# RLCD_SCH_28LED_v1p13p2.net
KiCad netlist of a schematic drawn in Altium Designer
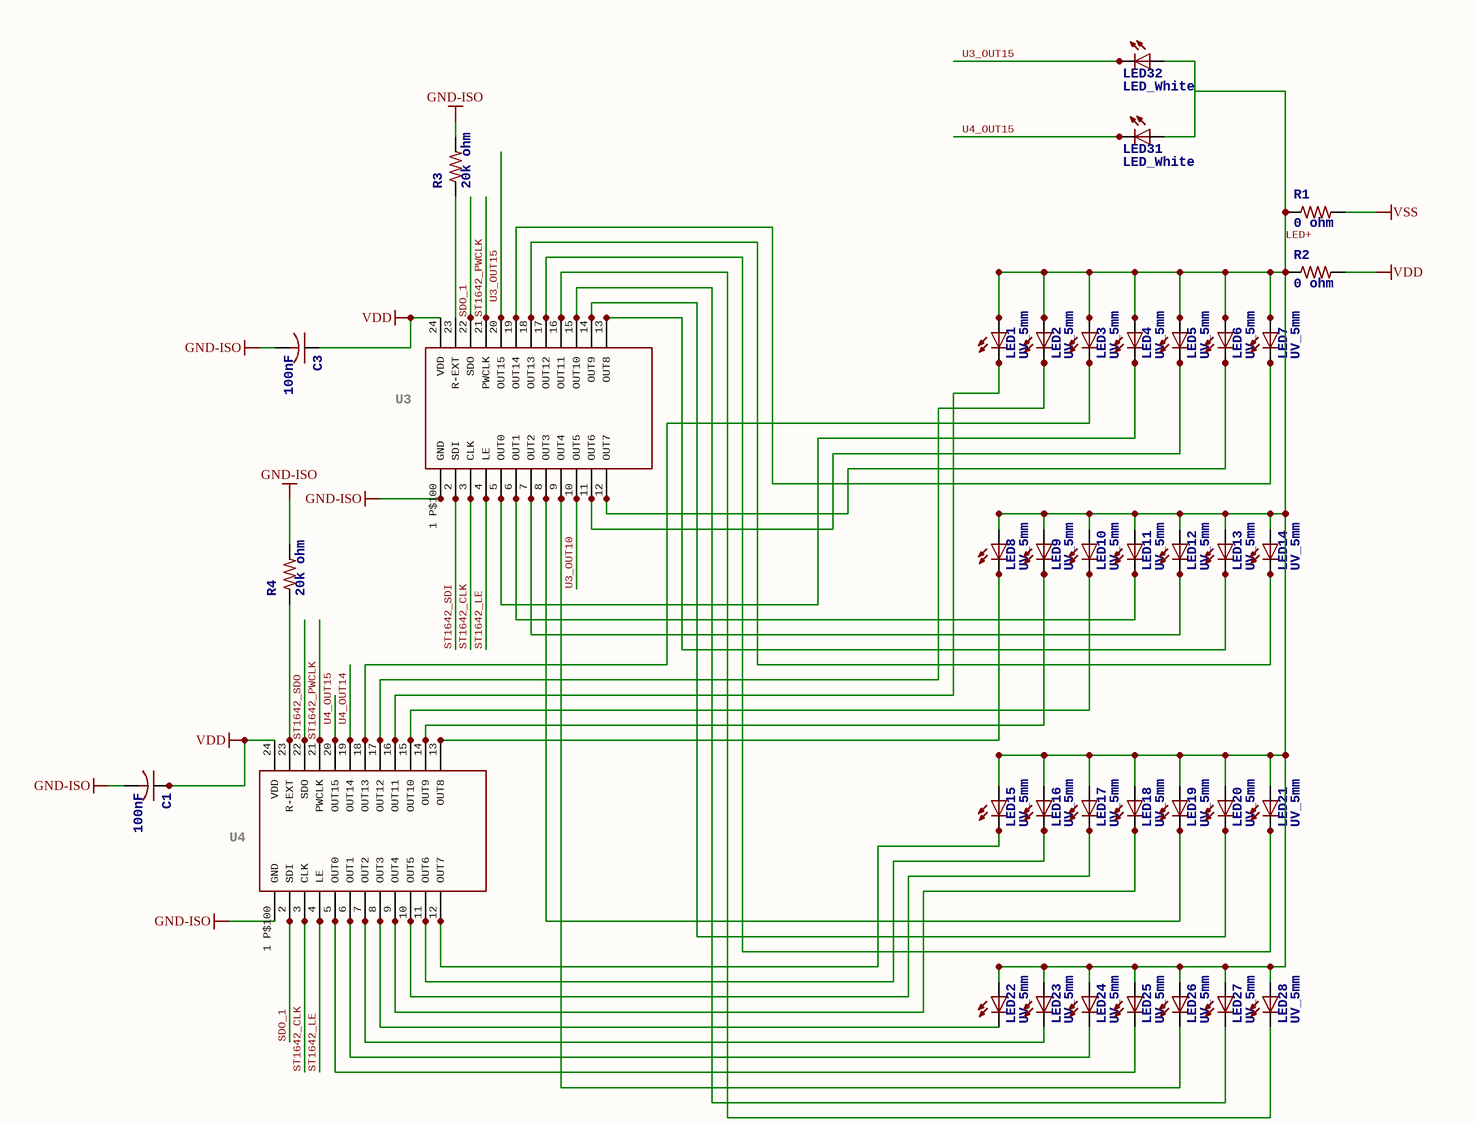
[diagram p0: RLCD_SCH_28LED_v1p13p2.SchDoc, top left]
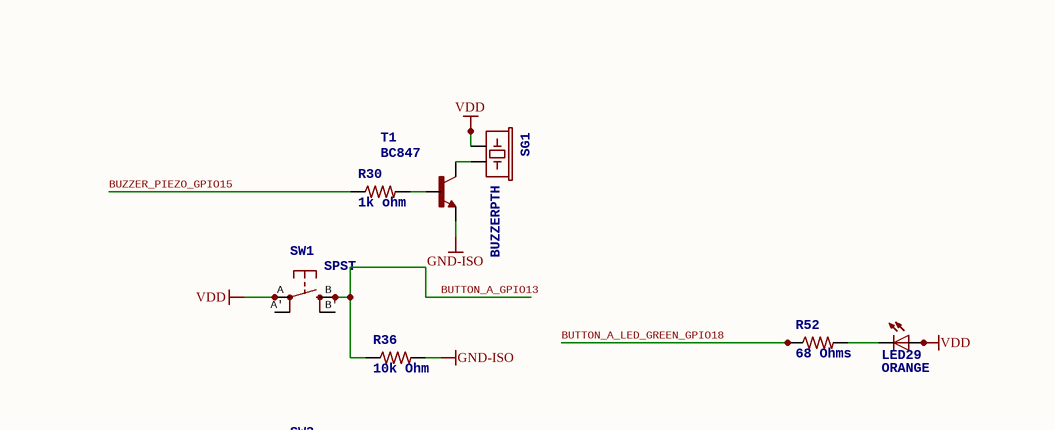
[diagram p1: RLCD_SCH_28LED_v1p13p2.SchDoc, top right]
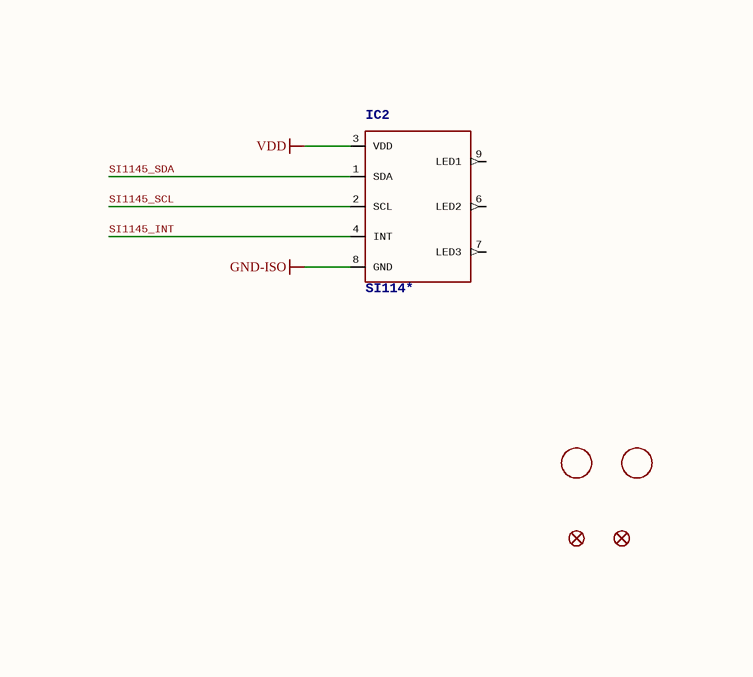
[diagram p2: RLCD_SCH_28LED_v1p13p2.SchDoc, bottom left]
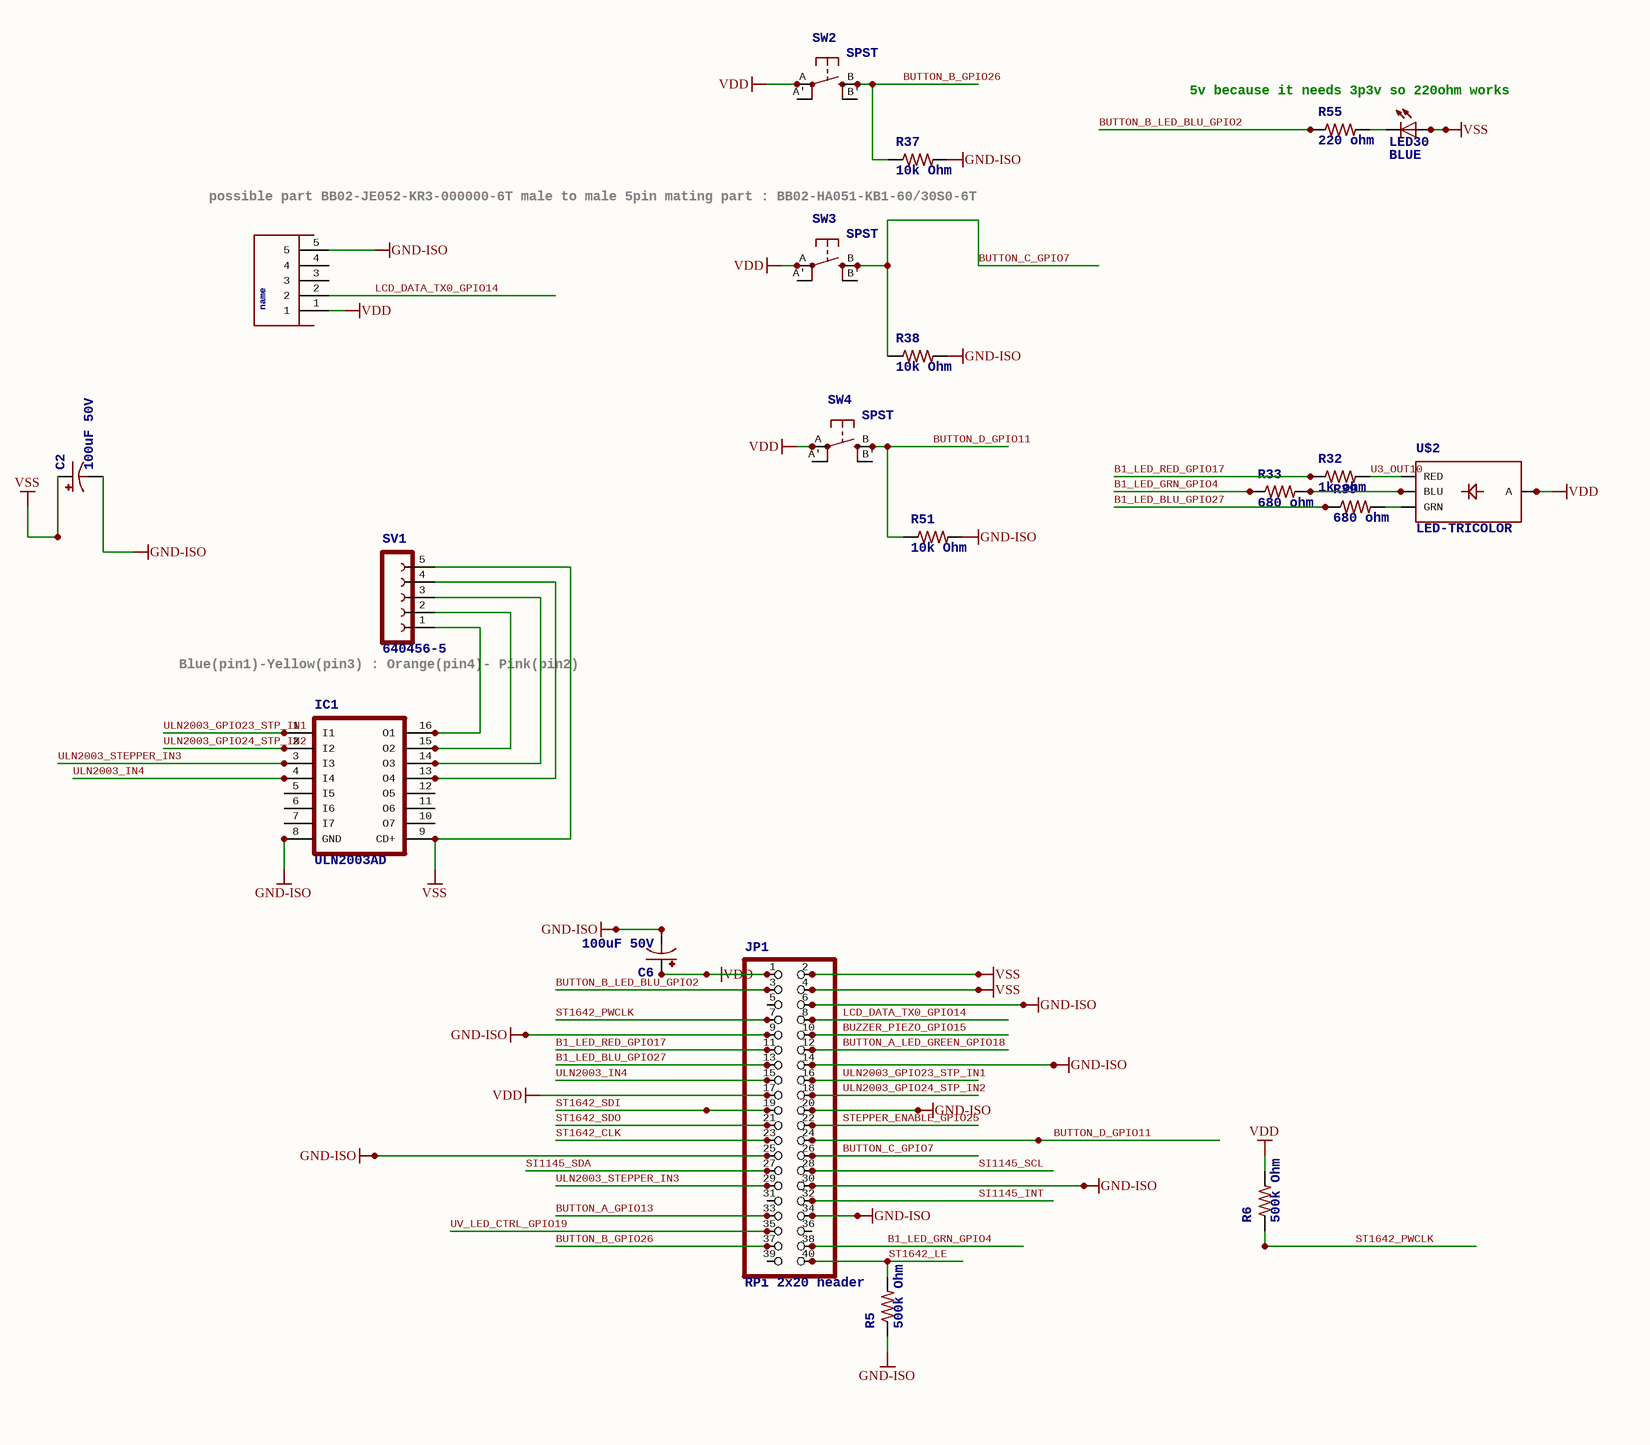
[diagram p3: RLCD_SCH_28LED_v1p13p2.SchDoc, bottom right]

(export (version "E")
  (design (tool "Eeschema 10.0.6"))
  (components
    (comp (ref "C1")
      (value "100nF")
      (footprint "C0805")
      (description "<B>CAPACITOR</B>, American symbol")
      (fields (field (name ">NAME") "C1") (field (name ">VALUE") "100nF"))
      (libsource (lib "resistor") (part "C-USC0805"))
    )
    (comp (ref "C2")
      (value "100uF 50V")
      (footprint "E3,5-8")
      (description "<B>POLARIZED CAPACITOR</B>, American symbol")
      (fields
        (field (name "PARTNO") "REA101M1HBK-0811P")
        (field (name ">NAME") "C2")
        (field (name ">VALUE") "100uF 50V")
      )
      (libsource (lib "") (part "CPOL-USE3.5-8_1"))
    )
    (comp (ref "C3")
      (value "100nF")
      (footprint "C0805")
      (description "<B>CAPACITOR</B>, American symbol")
      (fields (field (name ">NAME") "C3") (field (name ">VALUE") "100nF"))
      (libsource (lib "resistor") (part "C-USC0805"))
    )
    (comp (ref "C6")
      (value "100uF 50V")
      (footprint "E3,5-8")
      (description "<B>POLARIZED CAPACITOR</B>, American symbol")
      (fields
        (field (name "PARTNO") "REA101M1HBK-0811P")
        (field (name ">NAME") "C6")
        (field (name ">VALUE") "100uF 50V")
      )
      (libsource (lib "adafruit") (part "CPOL-USE3.5-8"))
    )
    (comp (ref "FID1")
      (value "FIDUCIAL1X2")
      (footprint "FIDUCIAL-1X2")
      (description "<b>Fiducial Alignment Points</b>\nVarious fiducial points for machine vision alignment.")
      (libsource (lib "SparkFun-Aesthetics") (part "FIDUCIAL1X2"))
    )
    (comp (ref "FID2")
      (value "FIDUCIAL1X2")
      (footprint "FIDUCIAL-1X2")
      (description "<b>Fiducial Alignment Points</b>\nVarious fiducial points for machine vision alignment.")
      (libsource (lib "SparkFun-Aesthetics") (part "FIDUCIAL1X2"))
    )
    (comp (ref "IC1")
      (value "ULN2003AD")
      (footprint "SO16")
      (description "<b>DRIVER ARRAY</b>")
      (fields (field (name ">NAME") "IC1") (field (name ">VALUE") "ULN2003AD"))
      (libsource (lib "uln-udn") (part "ULN2003AD"))
    )
    (comp (ref "IC2")
      (value "SI114*")
      (footprint "QFN-10")
      (fields (field (name ">NAME") "IC2") (field (name ">VALUE") "SI114*"))
      (libsource (lib "silabs") (part "SI114*"))
    )
    (comp (ref "JP1")
      (value "RPi 2x20 header")
      (footprint "2X20")
      (description "<b>PIN HEADER</b>")
      (fields
        (field (name "PARTNO") "929975-01-13-RK")
        (field (name ">NAME") "JP1")
        (field (name ">VALUE") "RPi 2x20 header")
      )
      (libsource (lib "adafruit") (part "PINHD-2X20"))
    )
    (comp (ref "LED1")
      (value "UV_5mm")
      (footprint "LED5MM")
      (fields (field (name ">NAME") "LED1") (field (name ">VALUE") "UV_5mm"))
      (libsource (lib "led") (part "LED5MM"))
    )
    (comp (ref "LED2")
      (value "UV_5mm")
      (footprint "LED5MM")
      (fields (field (name ">NAME") "LED2") (field (name ">VALUE") "UV_5mm"))
      (libsource (lib "led") (part "LED5MM"))
    )
    (comp (ref "LED3")
      (value "UV_5mm")
      (footprint "LED5MM")
      (fields (field (name ">NAME") "LED3") (field (name ">VALUE") "UV_5mm"))
      (libsource (lib "led") (part "LED5MM"))
    )
    (comp (ref "LED4")
      (value "UV_5mm")
      (footprint "LED5MM")
      (fields (field (name ">NAME") "LED4") (field (name ">VALUE") "UV_5mm"))
      (libsource (lib "led") (part "LED5MM"))
    )
    (comp (ref "LED5")
      (value "UV_5mm")
      (footprint "LED5MM")
      (fields (field (name ">NAME") "LED5") (field (name ">VALUE") "UV_5mm"))
      (libsource (lib "led") (part "LED5MM"))
    )
    (comp (ref "LED6")
      (value "UV_5mm")
      (footprint "LED5MM")
      (fields (field (name ">NAME") "LED6") (field (name ">VALUE") "UV_5mm"))
      (libsource (lib "led") (part "LED5MM"))
    )
    (comp (ref "LED7")
      (value "UV_5mm")
      (footprint "LED5MM")
      (fields (field (name ">NAME") "LED7") (field (name ">VALUE") "UV_5mm"))
      (libsource (lib "led") (part "LED5MM"))
    )
    (comp (ref "LED8")
      (value "UV_5mm")
      (footprint "LED5MM")
      (fields (field (name ">NAME") "LED8") (field (name ">VALUE") "UV_5mm"))
      (libsource (lib "led") (part "LED5MM"))
    )
    (comp (ref "LED9")
      (value "UV_5mm")
      (footprint "LED5MM")
      (fields (field (name ">NAME") "LED9") (field (name ">VALUE") "UV_5mm"))
      (libsource (lib "led") (part "LED5MM"))
    )
    (comp (ref "LED10")
      (value "UV_5mm")
      (footprint "LED5MM")
      (fields (field (name ">NAME") "LED10") (field (name ">VALUE") "UV_5mm"))
      (libsource (lib "led") (part "LED5MM"))
    )
    (comp (ref "LED11")
      (value "UV_5mm")
      (footprint "LED5MM")
      (fields (field (name ">NAME") "LED11") (field (name ">VALUE") "UV_5mm"))
      (libsource (lib "led") (part "LED5MM"))
    )
    (comp (ref "LED12")
      (value "UV_5mm")
      (footprint "LED5MM")
      (fields (field (name ">NAME") "LED12") (field (name ">VALUE") "UV_5mm"))
      (libsource (lib "led") (part "LED5MM"))
    )
    (comp (ref "LED13")
      (value "UV_5mm")
      (footprint "LED5MM")
      (fields (field (name ">NAME") "LED13") (field (name ">VALUE") "UV_5mm"))
      (libsource (lib "led") (part "LED5MM"))
    )
    (comp (ref "LED14")
      (value "UV_5mm")
      (footprint "LED5MM")
      (fields (field (name ">NAME") "LED14") (field (name ">VALUE") "UV_5mm"))
      (libsource (lib "led") (part "LED5MM"))
    )
    (comp (ref "LED15")
      (value "UV_5mm")
      (footprint "LED5MM")
      (fields (field (name ">NAME") "LED15") (field (name ">VALUE") "UV_5mm"))
      (libsource (lib "led") (part "LED5MM"))
    )
    (comp (ref "LED16")
      (value "UV_5mm")
      (footprint "LED5MM")
      (fields (field (name ">NAME") "LED16") (field (name ">VALUE") "UV_5mm"))
      (libsource (lib "led") (part "LED5MM"))
    )
    (comp (ref "LED17")
      (value "UV_5mm")
      (footprint "LED5MM")
      (fields (field (name ">NAME") "LED17") (field (name ">VALUE") "UV_5mm"))
      (libsource (lib "led") (part "LED5MM"))
    )
    (comp (ref "LED18")
      (value "UV_5mm")
      (footprint "LED5MM")
      (fields (field (name ">NAME") "LED18") (field (name ">VALUE") "UV_5mm"))
      (libsource (lib "led") (part "LED5MM"))
    )
    (comp (ref "LED19")
      (value "UV_5mm")
      (footprint "LED5MM")
      (fields (field (name ">NAME") "LED19") (field (name ">VALUE") "UV_5mm"))
      (libsource (lib "led") (part "LED5MM"))
    )
    (comp (ref "LED20")
      (value "UV_5mm")
      (footprint "LED5MM")
      (fields (field (name ">NAME") "LED20") (field (name ">VALUE") "UV_5mm"))
      (libsource (lib "led") (part "LED5MM"))
    )
    (comp (ref "LED21")
      (value "UV_5mm")
      (footprint "LED5MM")
      (fields (field (name ">NAME") "LED21") (field (name ">VALUE") "UV_5mm"))
      (libsource (lib "led") (part "LED5MM"))
    )
    (comp (ref "LED22")
      (value "UV_5mm")
      (footprint "LED5MM")
      (fields (field (name ">NAME") "LED22") (field (name ">VALUE") "UV_5mm"))
      (libsource (lib "led") (part "LED5MM"))
    )
    (comp (ref "LED23")
      (value "UV_5mm")
      (footprint "LED5MM")
      (fields (field (name ">NAME") "LED23") (field (name ">VALUE") "UV_5mm"))
      (libsource (lib "led") (part "LED5MM"))
    )
    (comp (ref "LED24")
      (value "UV_5mm")
      (footprint "LED5MM")
      (fields (field (name ">NAME") "LED24") (field (name ">VALUE") "UV_5mm"))
      (libsource (lib "led") (part "LED5MM"))
    )
    (comp (ref "LED25")
      (value "UV_5mm")
      (footprint "LED5MM")
      (fields (field (name ">NAME") "LED25") (field (name ">VALUE") "UV_5mm"))
      (libsource (lib "led") (part "LED5MM"))
    )
    (comp (ref "LED26")
      (value "UV_5mm")
      (footprint "LED5MM")
      (fields (field (name ">NAME") "LED26") (field (name ">VALUE") "UV_5mm"))
      (libsource (lib "led") (part "LED5MM"))
    )
    (comp (ref "LED27")
      (value "UV_5mm")
      (footprint "LED5MM")
      (fields (field (name ">NAME") "LED27") (field (name ">VALUE") "UV_5mm"))
      (libsource (lib "led") (part "LED5MM"))
    )
    (comp (ref "LED28")
      (value "UV_5mm")
      (footprint "LED5MM")
      (fields (field (name ">NAME") "LED28") (field (name ">VALUE") "UV_5mm"))
      (libsource (lib "led") (part "LED5MM"))
    )
    (comp (ref "LED29")
      (value "ORANGE")
      (footprint "CHIPLED_1206")
      (fields
        (field (name "PARTNO") "LG N971-KN-1")
        (field (name ">NAME") "LED29")
        (field (name ">VALUE") "ORANGE")
      )
      (libsource (lib "adafruit") (part "LEDCHIPLED_1206"))
    )
    (comp (ref "LED30")
      (value "BLUE")
      (footprint "CHIPLED_1206")
      (fields
        (field (name "PARTNO") "LTST-C21TBKT")
        (field (name ">NAME") "LED30")
        (field (name ">VALUE") "BLUE")
      )
      (libsource (lib "adafruit") (part "LEDCHIPLED_1206"))
    )
    (comp (ref "LED31")
      (value "LED_White")
      (footprint "CHIPLED_1206")
      (fields
        (field (name "PARTNO") "LG N971-KN-1")
        (field (name ">NAME") "LED31")
        (field (name ">VALUE") "LED_White")
      )
      (libsource (lib "adafruit") (part "LEDCHIPLED_1206"))
    )
    (comp (ref "LED32")
      (value "LED_White")
      (footprint "CHIPLED_1206")
      (fields
        (field (name "PARTNO") "LG N971-KN-1")
        (field (name ">NAME") "LED32")
        (field (name ">VALUE") "LED_White")
      )
      (libsource (lib "adafruit") (part "LEDCHIPLED_1206"))
    )
    (comp (ref "R1")
      (value "0 ohm")
      (footprint "0805")
      (description "<b>Resistor</b>\nBasic schematic elements and footprints for 0603, 1206, and PTH resistors.")
      (fields (field (name "PARTNO") "DNP") (field (name ">NAME") "R1") (field (name ">VALUE") "0 ohm"))
      (libsource (lib "SparkFun-Passives") (part "RESISTOR0805-RES"))
    )
    (comp (ref "R2")
      (value "0 ohm")
      (footprint "0805")
      (description "<b>Resistor</b>\nBasic schematic elements and footprints for 0603, 1206, and PTH resistors.")
      (fields (field (name "PARTNO") "DNP") (field (name ">NAME") "R2") (field (name ">VALUE") "0 ohm"))
      (libsource (lib "SparkFun-Passives") (part "RESISTOR0805-RES"))
    )
    (comp (ref "R3")
      (value "20k ohm")
      (footprint "0805")
      (description "<b>Resistor</b>\nBasic schematic elements and footprints for 0603, 1206, and PTH resistors.")
      (fields (field (name "PARTNO") "DNP") (field (name ">NAME") "R3") (field (name ">VALUE") "20k ohm"))
      (libsource (lib "SparkFun-Passives") (part "RESISTOR0805-RES"))
    )
    (comp (ref "R4")
      (value "20k ohm")
      (footprint "0805")
      (description "<b>Resistor</b>\nBasic schematic elements and footprints for 0603, 1206, and PTH resistors.")
      (fields (field (name "PARTNO") "DNP") (field (name ">NAME") "R4") (field (name ">VALUE") "20k ohm"))
      (libsource (lib "SparkFun-Passives") (part "RESISTOR0805-RES"))
    )
    (comp (ref "R5")
      (value "500k Ohm")
      (footprint "0805")
      (description "<b>Resistor</b>\nBasic schematic elements and footprints for 0603, 1206, and PTH resistors.")
      (fields
        (field (name "PARTNO") "RK73B2ATTD103J")
        (field (name ">NAME") "R5")
        (field (name ">VALUE") "500k Ohm")
      )
      (libsource (lib "SparkFun-Passives") (part "RESISTOR0805-RES"))
    )
    (comp (ref "R6")
      (value "500k Ohm")
      (footprint "0805")
      (description "<b>Resistor</b>\nBasic schematic elements and footprints for 0603, 1206, and PTH resistors.")
      (fields
        (field (name "PARTNO") "RK73B2ATTD103J")
        (field (name ">NAME") "R6")
        (field (name ">VALUE") "500k Ohm")
      )
      (libsource (lib "SparkFun-Passives") (part "RESISTOR0805-RES"))
    )
    (comp (ref "R30")
      (value "1k ohm")
      (footprint "0805")
      (description "<b>Resistor</b>\nBasic schematic elements and footprints for 0603, 1206, and PTH resistors.")
      (fields
        (field (name "PARTNO") "RK73H2ATTD1001F")
        (field (name ">NAME") "R30")
        (field (name ">VALUE") "1k ohm")
      )
      (libsource (lib "SparkFun-Passives") (part "RESISTOR0805-RES"))
    )
    (comp (ref "R32")
      (value "1k ohm")
      (footprint "0805")
      (description "<b>Resistor</b>\nBasic schematic elements and footprints for 0603, 1206, and PTH resistors.")
      (fields
        (field (name "PARTNO") "RK73H2ATTD1001F")
        (field (name ">NAME") "R32")
        (field (name ">VALUE") "1k ohm")
      )
      (libsource (lib "SparkFun-Passives") (part "RESISTOR0805-RES"))
    )
    (comp (ref "R33")
      (value "680 ohm")
      (footprint "0805")
      (description "<b>Resistor</b>\nBasic schematic elements and footprints for 0603, 1206, and PTH resistors.")
      (fields
        (field (name "PARTNO") "RK73B2ATTD681J")
        (field (name ">NAME") "R33")
        (field (name ">VALUE") "680 ohm")
      )
      (libsource (lib "SparkFun-Passives") (part "RESISTOR0805-RES"))
    )
    (comp (ref "R36")
      (value "10k Ohm")
      (footprint "0805")
      (description "<b>Resistor</b>\nBasic schematic elements and footprints for 0603, 1206, and PTH resistors.")
      (fields
        (field (name "PARTNO") "RK73B2ATTD103J")
        (field (name ">NAME") "R36")
        (field (name ">VALUE") "10k Ohm")
      )
      (libsource (lib "SparkFun-Passives") (part "RESISTOR0805-RES"))
    )
    (comp (ref "R37")
      (value "10k Ohm")
      (footprint "0805")
      (description "<b>Resistor</b>\nBasic schematic elements and footprints for 0603, 1206, and PTH resistors.")
      (fields
        (field (name "PARTNO") "RK73B2ATTD103J")
        (field (name ">NAME") "R37")
        (field (name ">VALUE") "10k Ohm")
      )
      (libsource (lib "SparkFun-Passives") (part "RESISTOR0805-RES"))
    )
    (comp (ref "R38")
      (value "10k Ohm")
      (footprint "0805")
      (description "<b>Resistor</b>\nBasic schematic elements and footprints for 0603, 1206, and PTH resistors.")
      (fields
        (field (name "PARTNO") "RK73B2ATTD103J")
        (field (name ">NAME") "R38")
        (field (name ">VALUE") "10k Ohm")
      )
      (libsource (lib "SparkFun-Passives") (part "RESISTOR0805-RES"))
    )
    (comp (ref "R39")
      (value "680 ohm")
      (footprint "0805")
      (description "<b>Resistor</b>\nBasic schematic elements and footprints for 0603, 1206, and PTH resistors.")
      (fields
        (field (name "PARTNO") "RK73B2ATTD681J")
        (field (name ">NAME") "R39")
        (field (name ">VALUE") "680 ohm")
      )
      (libsource (lib "SparkFun-Passives") (part "RESISTOR0805-RES"))
    )
    (comp (ref "R51")
      (value "10k Ohm")
      (footprint "0805")
      (description "<b>Resistor</b>\nBasic schematic elements and footprints for 0603, 1206, and PTH resistors.")
      (fields
        (field (name "PARTNO") "RK73B2ATTD103J")
        (field (name ">NAME") "R51")
        (field (name ">VALUE") "10k Ohm")
      )
      (libsource (lib "SparkFun-Passives") (part "RESISTOR0805-RES"))
    )
    (comp (ref "R52")
      (value "68 Ohms")
      (footprint "0805")
      (description "<b>Resistor</b>\nBasic schematic elements and footprints for 0603, 1206, and PTH resistors.")
      (fields
        (field (name "PARTNO") "RK73B2ATTDD121J")
        (field (name ">NAME") "R52")
        (field (name ">VALUE") "68 Ohms")
      )
      (libsource (lib "SparkFun-Passives") (part "RESISTOR0805-RES"))
    )
    (comp (ref "R55")
      (value "220 ohm")
      (footprint "0805")
      (description "<b>Resistor</b>\nBasic schematic elements and footprints for 0603, 1206, and PTH resistors.")
      (fields
        (field (name "PARTNO") "RK73B2ATTD221J")
        (field (name ">NAME") "R55")
        (field (name ">VALUE") "220 ohm")
      )
      (libsource (lib "SparkFun-Passives") (part "RESISTOR0805-RES"))
    )
    (comp (ref "SG1")
      (value "BUZZERPTH")
      (footprint "BUZZER-12MM")
      (description "<b>Buzzer 12mm</b>\nSpark Fun Electronics SKU : Comp-Buzzer")
      (fields
        (field (name "PARTNO") "AT-1220-TT-R")
        (field (name ">NAME") "SG1")
        (field (name ">VALUE") "BUZZERPTH")
      )
      (libsource (lib "SparkFun-Electromechanical") (part "BUZZERPTH"))
    )
    (comp (ref "SV1")
      (value "640456-5")
      (footprint "FE05-1")
      (description "<b>FEMALE HEADER</b>")
      (fields (field (name ">VALUE") "640456-5") (field (name ">NAME") "SV1"))
      (libsource (lib "con-lsta") (part "FE05-1"))
    )
    (comp (ref "SV3_LCD_HEADER")
      (value "22-05-2051")
      (footprint "MDF7-5S-2.54DSA")
      (fields (field (name "PARTNO") "MDF7-5S-2.54DSA(55)") (field (name "NAME") "name"))
      (libsource (lib "Trents_Hirose_5pin_2.54mm_Connector") (part "MDF7-5S-2.54DSA"))
    )
    (comp (ref "SW1")
      (value "SPST")
      (footprint "EVQ-Q2")
      (description "SMT 6mm switch, EVQQ2 series\n<p>http://www.ladyada.net/library/eagle</p>")
      (fields (field (name ">NAME") "SW1") (field (name ">VALUE") "SPST"))
      (libsource (lib "adafruit") (part "SPST_TACT-EVQQ2"))
    )
    (comp (ref "SW2")
      (value "SPST")
      (footprint "EVQ-Q2")
      (description "SMT 6mm switch, EVQQ2 series\n<p>http://www.ladyada.net/library/eagle</p>")
      (fields (field (name ">NAME") "SW2") (field (name ">VALUE") "SPST"))
      (libsource (lib "adafruit") (part "SPST_TACT-EVQQ2"))
    )
    (comp (ref "SW3")
      (value "SPST")
      (footprint "EVQ-Q2")
      (description "SMT 6mm switch, EVQQ2 series\n<p>http://www.ladyada.net/library/eagle</p>")
      (fields (field (name ">NAME") "SW3") (field (name ">VALUE") "SPST"))
      (libsource (lib "adafruit") (part "SPST_TACT-EVQQ2"))
    )
    (comp (ref "SW4")
      (value "SPST")
      (footprint "EVQ-Q2")
      (description "SMT 6mm switch, EVQQ2 series\n<p>http://www.ladyada.net/library/eagle</p>")
      (fields (field (name ">NAME") "SW4") (field (name ">VALUE") "SPST"))
      (libsource (lib "adafruit") (part "SPST_TACT-EVQQ2"))
    )
    (comp (ref "T1")
      (value "BC847")
      (footprint "SOT23")
      (description "<b>NPN TRANSISTOR</b>")
      (fields
        (field (name "PARTNO") "MMUN2214LT1G")
        (field (name ">NAME") "T1")
        (field (name ">VALUE") "BC847")
      )
      (libsource (lib "transistor") (part "BC847"))
    )
    (comp (ref "U$1")
      (value "FIDUCIAL")
      (footprint "FIDUCIAL_1MM")
      (description "For use by pick and place machines to calibrate the vision/machine, 1mm\n<p>By microbuilder.eu</p>")
      (libsource (lib "adafruit") (part "FIDUCIAL"))
    )
    (comp (ref "U$2")
      (value "LED-TRICOLOR")
      (footprint "LED-TRICOLOR-SMD")
      (fields
        (field (name "PARTNO") "CLV1A-FKB-CHMKPEHBB7A363")
        (field (name ">NAME") "U$2")
        (field (name ">VALUE") "LED-TRICOLOR")
      )
      (libsource (lib "SparkFun-LED") (part "LED-TRICOLOR"))
    )
    (comp (ref "U$3")
      (value "LED1642GWTTR")
      (footprint "TSSOP24")
      (libsource (lib "iBox_Nano_Custom_Components") (part "LED1642GWTTR"))
    )
    (comp (ref "U$4")
      (value "LED1642GWTTR")
      (footprint "TSSOP24")
      (libsource (lib "iBox_Nano_Custom_Components") (part "LED1642GWTTR"))
    )
    (comp (ref "U$5")
      (value "FIDUCIAL")
      (footprint "FIDUCIAL_1MM")
      (description "For use by pick and place machines to calibrate the vision/machine, 1mm\n<p>By microbuilder.eu</p>")
      (libsource (lib "adafruit") (part "FIDUCIAL"))
    )
  )
  (nets
    (net (code "1") (name "/B1_LED_BLU_GPIO27") (class "Default")
      (node (ref "JP1") (pin "13") (pinfunction "13_13") (pintype "passive"))
      (node (ref "R39") (pin "1") (pinfunction "1_1") (pintype "passive"))
    )
    (net (code "2") (name "/B1_LED_GRN_GPIO4") (class "Default")
      (node (ref "JP1") (pin "38") (pinfunction "38_38") (pintype "passive"))
      (node (ref "R33") (pin "1") (pinfunction "1_1") (pintype "passive"))
    )
    (net (code "3") (name "/B1_LED_RED_GPIO17") (class "Default")
      (node (ref "JP1") (pin "11") (pinfunction "11_11") (pintype "passive"))
      (node (ref "R32") (pin "1") (pinfunction "1_1") (pintype "passive"))
    )
    (net (code "4") (name "/BUTTON_A_GPIO13") (class "Default")
      (node (ref "JP1") (pin "33") (pinfunction "33_33") (pintype "passive"))
      (node (ref "R36") (pin "1") (pinfunction "1_1") (pintype "passive"))
      (node (ref "SW1") (pin "B") (pinfunction "S_B") (pintype "passive"))
    )
    (net (code "5") (name "/BUTTON_A_LED_GREEN_GPIO18") (class "Default")
      (node (ref "JP1") (pin "12") (pinfunction "12_12") (pintype "passive"))
      (node (ref "R52") (pin "1") (pinfunction "1_1") (pintype "passive"))
    )
    (net (code "6") (name "/BUTTON_B_GPIO26") (class "Default")
      (node (ref "JP1") (pin "37") (pinfunction "37_37") (pintype "passive"))
      (node (ref "R37") (pin "1") (pinfunction "1_1") (pintype "passive"))
      (node (ref "SW2") (pin "B") (pinfunction "S_B") (pintype "passive"))
    )
    (net (code "7") (name "/BUTTON_B_LED_BLU_GPIO2") (class "Default")
      (node (ref "JP1") (pin "3") (pinfunction "3_3") (pintype "passive"))
      (node (ref "R55") (pin "1") (pinfunction "1_1") (pintype "passive"))
    )
    (net (code "8") (name "/BUTTON_C_GPIO7") (class "Default")
      (node (ref "JP1") (pin "26") (pinfunction "26_26") (pintype "passive"))
      (node (ref "R38") (pin "1") (pinfunction "1_1") (pintype "passive"))
      (node (ref "SW3") (pin "B") (pinfunction "S_B") (pintype "passive"))
    )
    (net (code "9") (name "/BUTTON_D_GPIO11") (class "Default")
      (node (ref "JP1") (pin "24") (pinfunction "24_24") (pintype "passive"))
      (node (ref "R51") (pin "1") (pinfunction "1_1") (pintype "passive"))
      (node (ref "SW4") (pin "B") (pinfunction "S_B") (pintype "passive"))
    )
    (net (code "10") (name "/BUZZER_PIEZO_GPIO15") (class "Default")
      (node (ref "JP1") (pin "10") (pinfunction "10_10") (pintype "passive"))
      (node (ref "R30") (pin "1") (pinfunction "1_1") (pintype "passive"))
    )
    (net (code "11") (name "/LCD_DATA_TX0_GPIO14") (class "Default")
      (node (ref "JP1") (pin "8") (pinfunction "8_8") (pintype "passive"))
      (node (ref "SV3_LCD_HEADER") (pin "2") (pinfunction "2_2") (pintype "passive"))
    )
    (net (code "12") (name "/LED+") (class "Default")
      (node (ref "LED1") (pin "A") (pinfunction "A_A") (pintype "passive"))
      (node (ref "LED10") (pin "A") (pinfunction "A_A") (pintype "passive"))
      (node (ref "LED11") (pin "A") (pinfunction "A_A") (pintype "passive"))
      (node (ref "LED12") (pin "A") (pinfunction "A_A") (pintype "passive"))
      (node (ref "LED13") (pin "A") (pinfunction "A_A") (pintype "passive"))
      (node (ref "LED14") (pin "A") (pinfunction "A_A") (pintype "passive"))
      (node (ref "LED15") (pin "A") (pinfunction "A_A") (pintype "passive"))
      (node (ref "LED16") (pin "A") (pinfunction "A_A") (pintype "passive"))
      (node (ref "LED17") (pin "A") (pinfunction "A_A") (pintype "passive"))
      (node (ref "LED18") (pin "A") (pinfunction "A_A") (pintype "passive"))
      (node (ref "LED19") (pin "A") (pinfunction "A_A") (pintype "passive"))
      (node (ref "LED2") (pin "A") (pinfunction "A_A") (pintype "passive"))
      (node (ref "LED20") (pin "A") (pinfunction "A_A") (pintype "passive"))
      (node (ref "LED21") (pin "A") (pinfunction "A_A") (pintype "passive"))
      (node (ref "LED22") (pin "A") (pinfunction "A_A") (pintype "passive"))
      (node (ref "LED23") (pin "A") (pinfunction "A_A") (pintype "passive"))
      (node (ref "LED24") (pin "A") (pinfunction "A_A") (pintype "passive"))
      (node (ref "LED25") (pin "A") (pinfunction "A_A") (pintype "passive"))
      (node (ref "LED26") (pin "A") (pinfunction "A_A") (pintype "passive"))
      (node (ref "LED27") (pin "A") (pinfunction "A_A") (pintype "passive"))
      (node (ref "LED28") (pin "A") (pinfunction "A_A") (pintype "passive"))
      (node (ref "LED3") (pin "A") (pinfunction "A_A") (pintype "passive"))
      (node (ref "LED31") (pin "A") (pinfunction "A_A") (pintype "passive"))
      (node (ref "LED32") (pin "A") (pinfunction "A_A") (pintype "passive"))
      (node (ref "LED4") (pin "A") (pinfunction "A_A") (pintype "passive"))
      (node (ref "LED5") (pin "A") (pinfunction "A_A") (pintype "passive"))
      (node (ref "LED6") (pin "A") (pinfunction "A_A") (pintype "passive"))
      (node (ref "LED7") (pin "A") (pinfunction "A_A") (pintype "passive"))
      (node (ref "LED8") (pin "A") (pinfunction "A_A") (pintype "passive"))
      (node (ref "LED9") (pin "A") (pinfunction "A_A") (pintype "passive"))
      (node (ref "R1") (pin "1") (pinfunction "1_1") (pintype "passive"))
      (node (ref "R2") (pin "1") (pinfunction "1_1") (pintype "passive"))
    )
    (net (code "13") (name "/SDO_1") (class "Default")
      (node (ref "U$3") (pin "22") (pinfunction "SDO_22") (pintype "passive"))
      (node (ref "U$4") (pin "2") (pinfunction "SDI_2") (pintype "passive"))
    )
    (net (code "14") (name "/SI1145_INT") (class "Default")
      (node (ref "IC2") (pin "4") (pinfunction "INT_4") (pintype "open_collector"))
      (node (ref "JP1") (pin "32") (pinfunction "32_32") (pintype "passive"))
    )
    (net (code "15") (name "/SI1145_SCL") (class "Default")
      (node (ref "IC2") (pin "2") (pinfunction "SCL_2") (pintype "passive"))
      (node (ref "JP1") (pin "28") (pinfunction "28_28") (pintype "passive"))
    )
    (net (code "16") (name "/SI1145_SDA") (class "Default")
      (node (ref "IC2") (pin "1") (pinfunction "SDA_1") (pintype "passive"))
      (node (ref "JP1") (pin "27") (pinfunction "27_27") (pintype "passive"))
    )
    (net (code "17") (name "/ST1642_CLK") (class "Default")
      (node (ref "JP1") (pin "23") (pinfunction "23_23") (pintype "passive"))
      (node (ref "U$3") (pin "3") (pinfunction "CLK_3") (pintype "passive"))
      (node (ref "U$4") (pin "3") (pinfunction "CLK_3") (pintype "passive"))
    )
    (net (code "18") (name "/ST1642_LE") (class "Default")
      (node (ref "JP1") (pin "40") (pinfunction "40_40") (pintype "passive"))
      (node (ref "R5") (pin "2") (pinfunction "2_2") (pintype "passive"))
      (node (ref "U$3") (pin "4") (pinfunction "LE_4") (pintype "passive"))
      (node (ref "U$4") (pin "4") (pinfunction "LE_4") (pintype "passive"))
    )
    (net (code "19") (name "/ST1642_PWCLK") (class "Default")
      (node (ref "JP1") (pin "7") (pinfunction "7_7") (pintype "passive"))
      (node (ref "R6") (pin "1") (pinfunction "1_1") (pintype "passive"))
      (node (ref "U$3") (pin "21") (pinfunction "PWCLK_21") (pintype "passive"))
      (node (ref "U$4") (pin "21") (pinfunction "PWCLK_21") (pintype "passive"))
    )
    (net (code "20") (name "/ST1642_SDI") (class "Default")
      (node (ref "JP1") (pin "19") (pinfunction "19_19") (pintype "passive"))
      (node (ref "U$3") (pin "2") (pinfunction "SDI_2") (pintype "passive"))
    )
    (net (code "21") (name "/ST1642_SDO") (class "Default")
      (node (ref "JP1") (pin "21") (pinfunction "21_21") (pintype "passive"))
      (node (ref "U$4") (pin "22") (pinfunction "SDO_22") (pintype "passive"))
    )
    (net (code "22") (name "/STEPPER_ENABLE_GPIO25") (class "Default")
      (node (ref "JP1") (pin "22") (pinfunction "22_22") (pintype "passive"))
    )
    (net (code "23") (name "/U3_OUT10") (class "Default")
      (node (ref "R32") (pin "2") (pinfunction "2_2") (pintype "passive"))
      (node (ref "U$2") (pin "R") (pinfunction "RED_R") (pintype "passive"))
      (node (ref "U$3") (pin "10") (pinfunction "OUT5_10") (pintype "passive"))
    )
    (net (code "24") (name "/U3_OUT15") (class "Default")
      (node (ref "LED32") (pin "C") (pinfunction "C_C") (pintype "passive"))
      (node (ref "U$3") (pin "20") (pinfunction "OUT15_20") (pintype "passive"))
    )
    (net (code "25") (name "/U4_OUT14") (class "Default")
      (node (ref "U$4") (pin "19") (pinfunction "OUT14_19") (pintype "passive"))
    )
    (net (code "26") (name "/U4_OUT15") (class "Default")
      (node (ref "LED31") (pin "C") (pinfunction "C_C") (pintype "passive"))
      (node (ref "U$4") (pin "20") (pinfunction "OUT15_20") (pintype "passive"))
    )
    (net (code "27") (name "/ULN2003_GPIO23_STP_IN1") (class "Default")
      (node (ref "IC1") (pin "1") (pinfunction "I1_1") (pintype "passive"))
      (node (ref "JP1") (pin "16") (pinfunction "16_16") (pintype "passive"))
    )
    (net (code "28") (name "/ULN2003_GPIO24_STP_IN2") (class "Default")
      (node (ref "IC1") (pin "2") (pinfunction "I2_2") (pintype "passive"))
      (node (ref "JP1") (pin "18") (pinfunction "18_18") (pintype "passive"))
    )
    (net (code "29") (name "/ULN2003_IN4") (class "Default")
      (node (ref "IC1") (pin "4") (pinfunction "I4_4") (pintype "passive"))
      (node (ref "JP1") (pin "15") (pinfunction "15_15") (pintype "passive"))
    )
    (net (code "30") (name "/ULN2003_STEPPER_IN3") (class "Default")
      (node (ref "IC1") (pin "3") (pinfunction "I3_3") (pintype "passive"))
      (node (ref "JP1") (pin "29") (pinfunction "29_29") (pintype "passive"))
    )
    (net (code "31") (name "/UV_LED_CTRL_GPIO19") (class "Default")
      (node (ref "JP1") (pin "35") (pinfunction "35_35") (pintype "passive"))
    )
    (net (code "32") (name "GND-ISO") (class "Default")
      (node (ref "C1") (pin "2") (pinfunction "2_2") (pintype "passive"))
      (node (ref "C2") (pin "-") (pinfunction "-_-") (pintype "passive"))
      (node (ref "C3") (pin "2") (pinfunction "2_2") (pintype "passive"))
      (node (ref "C6") (pin "-") (pinfunction "-_-") (pintype "passive"))
      (node (ref "IC1") (pin "8") (pinfunction "GND_8") (pintype "power_in"))
      (node (ref "IC2") (pin "8") (pinfunction "GND_8") (pintype "power_in"))
      (node (ref "JP1") (pin "14") (pinfunction "14_14") (pintype "passive"))
      (node (ref "JP1") (pin "20") (pinfunction "20_20") (pintype "passive"))
      (node (ref "JP1") (pin "25") (pinfunction "25_25") (pintype "passive"))
      (node (ref "JP1") (pin "30") (pinfunction "30_30") (pintype "passive"))
      (node (ref "JP1") (pin "34") (pinfunction "34_34") (pintype "passive"))
      (node (ref "JP1") (pin "6") (pinfunction "6_6") (pintype "passive"))
      (node (ref "JP1") (pin "9") (pinfunction "9_9") (pintype "passive"))
      (node (ref "R3") (pin "2") (pinfunction "2_2") (pintype "passive"))
      (node (ref "R36") (pin "2") (pinfunction "2_2") (pintype "passive"))
      (node (ref "R37") (pin "2") (pinfunction "2_2") (pintype "passive"))
      (node (ref "R38") (pin "2") (pinfunction "2_2") (pintype "passive"))
      (node (ref "R4") (pin "2") (pinfunction "2_2") (pintype "passive"))
      (node (ref "R5") (pin "1") (pinfunction "1_1") (pintype "passive"))
      (node (ref "R51") (pin "2") (pinfunction "2_2") (pintype "passive"))
      (node (ref "SV3_LCD_HEADER") (pin "5") (pinfunction "5_5") (pintype "passive"))
      (node (ref "T1") (pin "2") (pinfunction "E_2") (pintype "passive"))
      (node (ref "U$3") (pin "1_P$100") (pinfunction "GND_1_P$100") (pintype "passive"))
      (node (ref "U$4") (pin "1_P$100") (pinfunction "GND_1_P$100") (pintype "passive"))
    )
    (net (code "33") (name "Net-(IC1-O1)") (class "Default")
      (node (ref "IC1") (pin "16") (pinfunction "O1_16") (pintype "open_collector"))
      (node (ref "SV1") (pin "1") (pinfunction "1_1") (pintype "passive"))
    )
    (net (code "34") (name "Net-(IC1-O2)") (class "Default")
      (node (ref "IC1") (pin "15") (pinfunction "O2_15") (pintype "open_collector"))
      (node (ref "SV1") (pin "2") (pinfunction "2_2") (pintype "passive"))
    )
    (net (code "35") (name "Net-(IC1-O3)") (class "Default")
      (node (ref "IC1") (pin "14") (pinfunction "O3_14") (pintype "open_collector"))
      (node (ref "SV1") (pin "3") (pinfunction "3_3") (pintype "passive"))
    )
    (net (code "36") (name "Net-(IC1-O4)") (class "Default")
      (node (ref "IC1") (pin "13") (pinfunction "O4_13") (pintype "open_collector"))
      (node (ref "SV1") (pin "4") (pinfunction "4_4") (pintype "passive"))
    )
    (net (code "37") (name "Net-(LED1-C)") (class "Default")
      (node (ref "LED1") (pin "K") (pinfunction "C_K") (pintype "passive"))
      (node (ref "U$4") (pin "16") (pinfunction "OUT11_16") (pintype "passive"))
    )
    (net (code "38") (name "Net-(LED2-C)") (class "Default")
      (node (ref "LED2") (pin "K") (pinfunction "C_K") (pintype "passive"))
      (node (ref "U$4") (pin "17") (pinfunction "OUT12_17") (pintype "passive"))
    )
    (net (code "39") (name "Net-(LED3-C)") (class "Default")
      (node (ref "LED3") (pin "K") (pinfunction "C_K") (pintype "passive"))
      (node (ref "U$4") (pin "18") (pinfunction "OUT13_18") (pintype "passive"))
    )
    (net (code "40") (name "Net-(LED4-C)") (class "Default")
      (node (ref "LED4") (pin "K") (pinfunction "C_K") (pintype "passive"))
      (node (ref "U$3") (pin "5") (pinfunction "OUT0_5") (pintype "passive"))
    )
    (net (code "41") (name "Net-(LED5-C)") (class "Default")
      (node (ref "LED5") (pin "K") (pinfunction "C_K") (pintype "passive"))
      (node (ref "U$3") (pin "11") (pinfunction "OUT6_11") (pintype "passive"))
    )
    (net (code "42") (name "Net-(LED6-C)") (class "Default")
      (node (ref "LED6") (pin "K") (pinfunction "C_K") (pintype "passive"))
      (node (ref "U$3") (pin "12") (pinfunction "OUT7_12") (pintype "passive"))
    )
    (net (code "43") (name "Net-(LED7-C)") (class "Default")
      (node (ref "LED7") (pin "K") (pinfunction "C_K") (pintype "passive"))
      (node (ref "U$3") (pin "19") (pinfunction "OUT14_19") (pintype "passive"))
    )
    (net (code "44") (name "Net-(LED8-C)") (class "Default")
      (node (ref "LED8") (pin "K") (pinfunction "C_K") (pintype "passive"))
      (node (ref "U$4") (pin "13") (pinfunction "OUT8_13") (pintype "passive"))
    )
    (net (code "45") (name "Net-(LED9-C)") (class "Default")
      (node (ref "LED9") (pin "K") (pinfunction "C_K") (pintype "passive"))
      (node (ref "U$4") (pin "14") (pinfunction "OUT9_14") (pintype "passive"))
    )
    (net (code "46") (name "Net-(LED10-C)") (class "Default")
      (node (ref "LED10") (pin "K") (pinfunction "C_K") (pintype "passive"))
      (node (ref "U$4") (pin "15") (pinfunction "OUT10_15") (pintype "passive"))
    )
    (net (code "47") (name "Net-(LED11-C)") (class "Default")
      (node (ref "LED11") (pin "K") (pinfunction "C_K") (pintype "passive"))
      (node (ref "U$3") (pin "6") (pinfunction "OUT1_6") (pintype "passive"))
    )
    (net (code "48") (name "Net-(LED12-C)") (class "Default")
      (node (ref "LED12") (pin "K") (pinfunction "C_K") (pintype "passive"))
      (node (ref "U$3") (pin "7") (pinfunction "OUT2_7") (pintype "passive"))
    )
    (net (code "49") (name "Net-(LED13-C)") (class "Default")
      (node (ref "LED13") (pin "K") (pinfunction "C_K") (pintype "passive"))
      (node (ref "U$3") (pin "13") (pinfunction "OUT8_13") (pintype "passive"))
    )
    (net (code "50") (name "Net-(LED14-C)") (class "Default")
      (node (ref "LED14") (pin "K") (pinfunction "C_K") (pintype "passive"))
      (node (ref "U$3") (pin "18") (pinfunction "OUT13_18") (pintype "passive"))
    )
    (net (code "51") (name "Net-(LED15-C)") (class "Default")
      (node (ref "LED15") (pin "K") (pinfunction "C_K") (pintype "passive"))
      (node (ref "U$4") (pin "12") (pinfunction "OUT7_12") (pintype "passive"))
    )
    (net (code "52") (name "Net-(LED16-C)") (class "Default")
      (node (ref "LED16") (pin "K") (pinfunction "C_K") (pintype "passive"))
      (node (ref "U$4") (pin "11") (pinfunction "OUT6_11") (pintype "passive"))
    )
    (net (code "53") (name "Net-(LED17-C)") (class "Default")
      (node (ref "LED17") (pin "K") (pinfunction "C_K") (pintype "passive"))
      (node (ref "U$4") (pin "10") (pinfunction "OUT5_10") (pintype "passive"))
    )
    (net (code "54") (name "Net-(LED18-C)") (class "Default")
      (node (ref "LED18") (pin "K") (pinfunction "C_K") (pintype "passive"))
      (node (ref "U$4") (pin "9") (pinfunction "OUT4_9") (pintype "passive"))
    )
    (net (code "55") (name "Net-(LED19-C)") (class "Default")
      (node (ref "LED19") (pin "K") (pinfunction "C_K") (pintype "passive"))
      (node (ref "U$3") (pin "8") (pinfunction "OUT3_8") (pintype "passive"))
    )
    (net (code "56") (name "Net-(LED20-C)") (class "Default")
      (node (ref "LED20") (pin "K") (pinfunction "C_K") (pintype "passive"))
      (node (ref "U$3") (pin "14") (pinfunction "OUT9_14") (pintype "passive"))
    )
    (net (code "57") (name "Net-(LED21-C)") (class "Default")
      (node (ref "LED21") (pin "K") (pinfunction "C_K") (pintype "passive"))
      (node (ref "U$3") (pin "17") (pinfunction "OUT12_17") (pintype "passive"))
    )
    (net (code "58") (name "Net-(LED22-C)") (class "Default")
      (node (ref "LED22") (pin "K") (pinfunction "C_K") (pintype "passive"))
      (node (ref "U$4") (pin "8") (pinfunction "OUT3_8") (pintype "passive"))
    )
    (net (code "59") (name "Net-(LED23-C)") (class "Default")
      (node (ref "LED23") (pin "K") (pinfunction "C_K") (pintype "passive"))
      (node (ref "U$4") (pin "7") (pinfunction "OUT2_7") (pintype "passive"))
    )
    (net (code "60") (name "Net-(LED24-C)") (class "Default")
      (node (ref "LED24") (pin "K") (pinfunction "C_K") (pintype "passive"))
      (node (ref "U$4") (pin "6") (pinfunction "OUT1_6") (pintype "passive"))
    )
    (net (code "61") (name "Net-(LED25-C)") (class "Default")
      (node (ref "LED25") (pin "K") (pinfunction "C_K") (pintype "passive"))
      (node (ref "U$4") (pin "5") (pinfunction "OUT0_5") (pintype "passive"))
    )
    (net (code "62") (name "Net-(LED26-C)") (class "Default")
      (node (ref "LED26") (pin "K") (pinfunction "C_K") (pintype "passive"))
      (node (ref "U$3") (pin "9") (pinfunction "OUT4_9") (pintype "passive"))
    )
    (net (code "63") (name "Net-(LED27-C)") (class "Default")
      (node (ref "LED27") (pin "K") (pinfunction "C_K") (pintype "passive"))
      (node (ref "U$3") (pin "15") (pinfunction "OUT10_15") (pintype "passive"))
    )
    (net (code "64") (name "Net-(LED28-C)") (class "Default")
      (node (ref "LED28") (pin "K") (pinfunction "C_K") (pintype "passive"))
      (node (ref "U$3") (pin "16") (pinfunction "OUT11_16") (pintype "passive"))
    )
    (net (code "65") (name "Net-(LED29-PadC)") (class "Default")
      (node (ref "LED29") (pin "C") (pinfunction "C_C") (pintype "passive"))
      (node (ref "R52") (pin "2") (pinfunction "2_2") (pintype "passive"))
    )
    (net (code "66") (name "Net-(LED30-PadC)") (class "Default")
      (node (ref "LED30") (pin "C") (pinfunction "C_C") (pintype "passive"))
      (node (ref "R55") (pin "2") (pinfunction "2_2") (pintype "passive"))
    )
    (net (code "67") (name "Net-(SG1-2)") (class "Default")
      (node (ref "SG1") (pin "-") (pinfunction "2_-") (pintype "passive"))
      (node (ref "T1") (pin "3") (pinfunction "C_3") (pintype "passive"))
    )
    (net (code "68") (name "Net-(T1-B)") (class "Default")
      (node (ref "R30") (pin "2") (pinfunction "2_2") (pintype "passive"))
      (node (ref "T1") (pin "1") (pinfunction "B_1") (pintype "passive"))
    )
    (net (code "69") (name "Net-(U$2-BLU)") (class "Default")
      (node (ref "R33") (pin "2") (pinfunction "2_2") (pintype "passive"))
      (node (ref "U$2") (pin "B") (pinfunction "BLU_B") (pintype "passive"))
    )
    (net (code "70") (name "Net-(U$2-GRN)") (class "Default")
      (node (ref "R39") (pin "2") (pinfunction "2_2") (pintype "passive"))
      (node (ref "U$2") (pin "G") (pinfunction "GRN_G") (pintype "passive"))
    )
    (net (code "71") (name "Net-(U$3-R-EXT)") (class "Default")
      (node (ref "R3") (pin "1") (pinfunction "1_1") (pintype "passive"))
      (node (ref "U$3") (pin "23") (pinfunction "R-EXT_23") (pintype "passive"))
    )
    (net (code "72") (name "Net-(U$4-R-EXT)") (class "Default")
      (node (ref "R4") (pin "1") (pinfunction "1_1") (pintype "passive"))
      (node (ref "U$4") (pin "23") (pinfunction "R-EXT_23") (pintype "passive"))
    )
    (net (code "73") (name "VDD") (class "Default")
      (node (ref "C1") (pin "1") (pinfunction "1_1") (pintype "passive"))
      (node (ref "C3") (pin "1") (pinfunction "1_1") (pintype "passive"))
      (node (ref "C6") (pin "+") (pinfunction "+_+") (pintype "passive"))
      (node (ref "IC2") (pin "3") (pinfunction "VDD_3") (pintype "power_in"))
      (node (ref "JP1") (pin "1") (pinfunction "1_1") (pintype "passive"))
      (node (ref "JP1") (pin "17") (pinfunction "17_17") (pintype "passive"))
      (node (ref "LED29") (pin "A") (pinfunction "A_A") (pintype "passive"))
      (node (ref "R2") (pin "2") (pinfunction "2_2") (pintype "passive"))
      (node (ref "R6") (pin "2") (pinfunction "2_2") (pintype "passive"))
      (node (ref "SG1") (pin "+") (pinfunction "1_+") (pintype "passive"))
      (node (ref "SV3_LCD_HEADER") (pin "1") (pinfunction "1_1") (pintype "passive"))
      (node (ref "SW1") (pin "A") (pinfunction "P_A") (pintype "passive"))
      (node (ref "SW2") (pin "A") (pinfunction "P_A") (pintype "passive"))
      (node (ref "SW3") (pin "A") (pinfunction "P_A") (pintype "passive"))
      (node (ref "SW4") (pin "A") (pinfunction "P_A") (pintype "passive"))
      (node (ref "U$2") (pin "A") (pinfunction "A_A") (pintype "passive"))
      (node (ref "U$3") (pin "24") (pinfunction "VDD_24") (pintype "passive"))
      (node (ref "U$4") (pin "24") (pinfunction "VDD_24") (pintype "passive"))
    )
    (net (code "74") (name "VSS") (class "Default")
      (node (ref "C2") (pin "+") (pinfunction "+_+") (pintype "passive"))
      (node (ref "IC1") (pin "9") (pinfunction "CD+_9") (pintype "passive"))
      (node (ref "JP1") (pin "2") (pinfunction "2_2") (pintype "passive"))
      (node (ref "JP1") (pin "4") (pinfunction "4_4") (pintype "passive"))
      (node (ref "LED30") (pin "A") (pinfunction "A_A") (pintype "passive"))
      (node (ref "R1") (pin "2") (pinfunction "2_2") (pintype "passive"))
      (node (ref "SV1") (pin "5") (pinfunction "5_5") (pintype "passive"))
    )
    (net (code "75") (name "unconnected-(IC1-I5-Pad5)") (class "Default")
      (node (ref "IC1") (pin "5") (pinfunction "I5_5") (pintype "passive"))
    )
    (net (code "76") (name "unconnected-(IC1-I6-Pad6)") (class "Default")
      (node (ref "IC1") (pin "6") (pinfunction "I6_6") (pintype "passive"))
    )
    (net (code "77") (name "unconnected-(IC1-I7-Pad7)") (class "Default")
      (node (ref "IC1") (pin "7") (pinfunction "I7_7") (pintype "passive"))
    )
    (net (code "78") (name "unconnected-(IC1-O5-Pad12)") (class "Default")
      (node (ref "IC1") (pin "12") (pinfunction "O5_12") (pintype "open_collector"))
    )
    (net (code "79") (name "unconnected-(IC1-O6-Pad11)") (class "Default")
      (node (ref "IC1") (pin "11") (pinfunction "O6_11") (pintype "open_collector"))
    )
    (net (code "80") (name "unconnected-(IC1-O7-Pad10)") (class "Default")
      (node (ref "IC1") (pin "10") (pinfunction "O7_10") (pintype "open_collector"))
    )
    (net (code "81") (name "unconnected-(IC2-LED1-Pad9)") (class "Default")
      (node (ref "IC2") (pin "9") (pinfunction "LED1_9") (pintype "output"))
    )
    (net (code "82") (name "unconnected-(IC2-LED2-Pad6)") (class "Default")
      (node (ref "IC2") (pin "6") (pinfunction "LED2_6") (pintype "output"))
    )
    (net (code "83") (name "unconnected-(IC2-LED3-Pad7)") (class "Default")
      (node (ref "IC2") (pin "7") (pinfunction "LED3_7") (pintype "output"))
    )
    (net (code "84") (name "unconnected-(JP1-Pad5)") (class "Default")
      (node (ref "JP1") (pin "5") (pinfunction "5_5") (pintype "passive"))
    )
    (net (code "85") (name "unconnected-(JP1-Pad31)") (class "Default")
      (node (ref "JP1") (pin "31") (pinfunction "31_31") (pintype "passive"))
    )
    (net (code "86") (name "unconnected-(JP1-Pad36)") (class "Default")
      (node (ref "JP1") (pin "36") (pinfunction "36_36") (pintype "passive"))
    )
    (net (code "87") (name "unconnected-(JP1-Pad39)") (class "Default")
      (node (ref "JP1") (pin "39") (pinfunction "39_39") (pintype "passive"))
    )
    (net (code "88") (name "unconnected-(SV3_LCD_HEADER-Pad3)") (class "Default")
      (node (ref "SV3_LCD_HEADER") (pin "3") (pinfunction "3_3") (pintype "passive"))
    )
    (net (code "89") (name "unconnected-(SV3_LCD_HEADER-Pad4)") (class "Default")
      (node (ref "SV3_LCD_HEADER") (pin "4") (pinfunction "4_4") (pintype "passive"))
    )
    (net (code "90") (name "unconnected-(SW1-P1-PadA')") (class "Default")
      (node (ref "SW1") (pin "A'") (pinfunction "P1_A'") (pintype "passive"))
    )
    (net (code "91") (name "unconnected-(SW1-S1-PadB')") (class "Default")
      (node (ref "SW1") (pin "B'") (pinfunction "S1_B'") (pintype "passive"))
    )
    (net (code "92") (name "unconnected-(SW2-P1-PadA')") (class "Default")
      (node (ref "SW2") (pin "A'") (pinfunction "P1_A'") (pintype "passive"))
    )
    (net (code "93") (name "unconnected-(SW2-S1-PadB')") (class "Default")
      (node (ref "SW2") (pin "B'") (pinfunction "S1_B'") (pintype "passive"))
    )
    (net (code "94") (name "unconnected-(SW3-P1-PadA')") (class "Default")
      (node (ref "SW3") (pin "A'") (pinfunction "P1_A'") (pintype "passive"))
    )
    (net (code "95") (name "unconnected-(SW3-S1-PadB')") (class "Default")
      (node (ref "SW3") (pin "B'") (pinfunction "S1_B'") (pintype "passive"))
    )
    (net (code "96") (name "unconnected-(SW4-P1-PadA')") (class "Default")
      (node (ref "SW4") (pin "A'") (pinfunction "P1_A'") (pintype "passive"))
    )
    (net (code "97") (name "unconnected-(SW4-S1-PadB')") (class "Default")
      (node (ref "SW4") (pin "B'") (pinfunction "S1_B'") (pintype "passive"))
    )
  )
)
